# avip-mod_v3.net
KiCad netlist of a schematic drawn in EAGLE
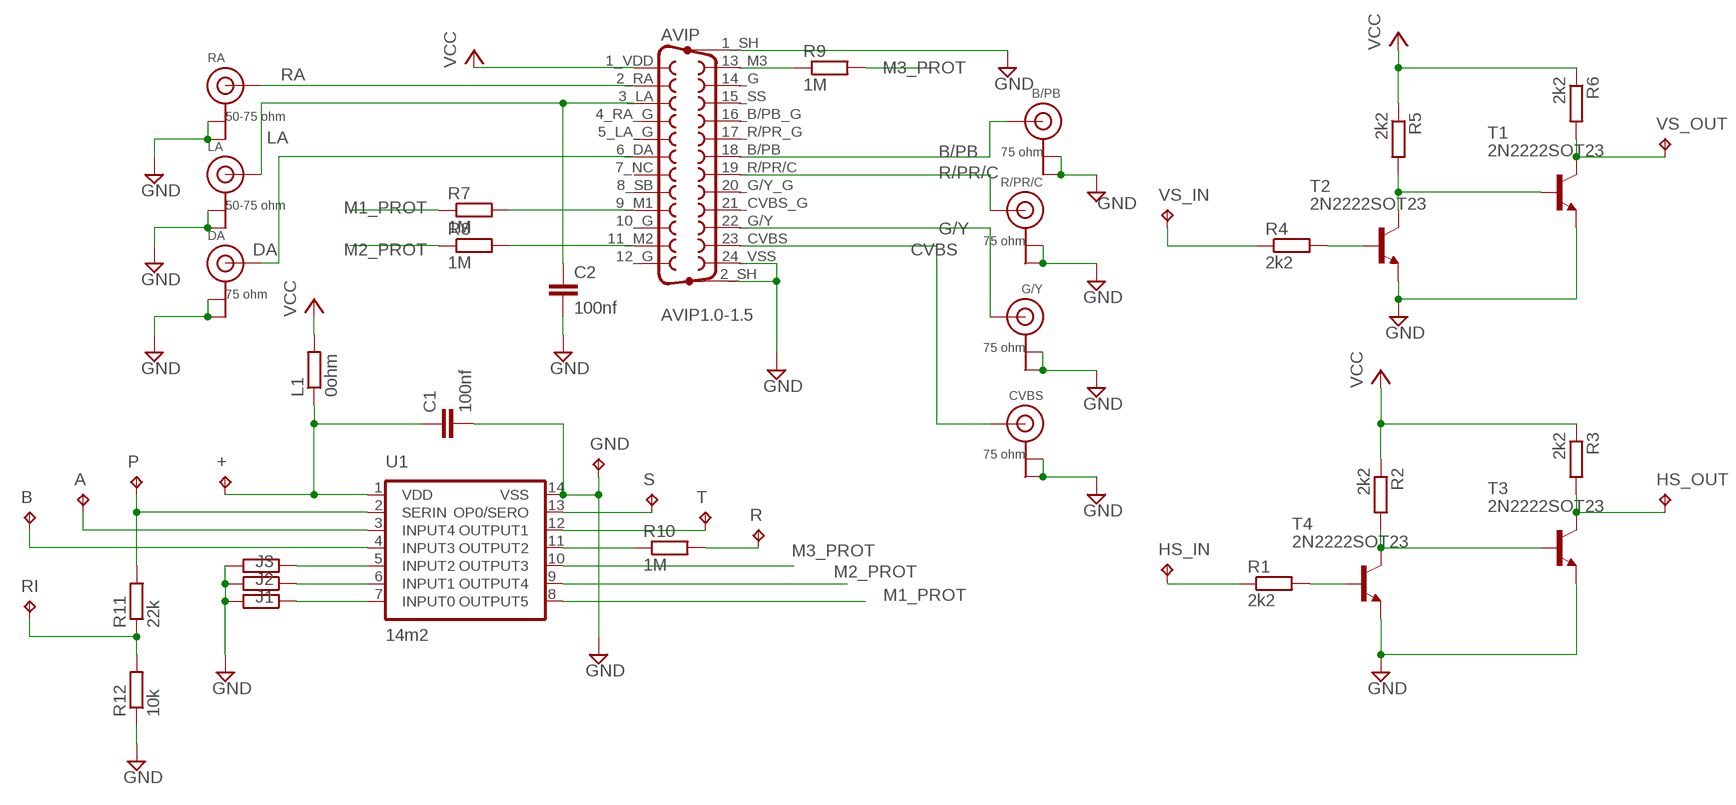
[diagram p0: schematic, sheet 1]

(export (version "E")
  (design (tool "Eeschema 10.0.6"))
  (components
    (comp (ref "+")
      (value "TPTP07SQ")
      (footprint "eagle-import:TP07SQ")
      (libsource (lib "eagle-import") (part "TPTP07SQ"))
    )
    (comp (ref "A")
      (value "TPTP07SQ")
      (footprint "eagle-import:TP07SQ")
      (libsource (lib "eagle-import") (part "TPTP07SQ"))
    )
    (comp (ref "AVIP")
      (value "AVIP1.0-1.5")
      (footprint "eagle-import:AVIP-1.0-1.5")
      (libsource (lib "eagle-import") (part "AVIP1.0-1.5"))
    )
    (comp (ref "B")
      (value "TPTP07SQ")
      (footprint "eagle-import:TP07SQ")
      (libsource (lib "eagle-import") (part "TPTP07SQ"))
    )
    (comp (ref "B/PB")
      (value "75 ohm")
      (footprint "eagle-import:U.FL")
      (libsource (lib "eagle-import") (part "ANTENNA_U.FL"))
    )
    (comp (ref "C1")
      (value "100nf")
      (footprint "eagle-import:C0603")
      (libsource (lib "eagle-import") (part "C-EUC0603"))
    )
    (comp (ref "C2")
      (value "100nf")
      (footprint "eagle-import:C0603")
      (libsource (lib "eagle-import") (part "C-EUC0603"))
    )
    (comp (ref "CVBS")
      (value "75 ohm")
      (footprint "eagle-import:U.FL")
      (libsource (lib "eagle-import") (part "ANTENNA_U.FL"))
    )
    (comp (ref "DA")
      (value "75 ohm")
      (footprint "eagle-import:U.FL")
      (libsource (lib "eagle-import") (part "ANTENNA_U.FL"))
    )
    (comp (ref "G/Y")
      (value "75 ohm")
      (footprint "eagle-import:U.FL")
      (libsource (lib "eagle-import") (part "ANTENNA_U.FL"))
    )
    (comp (ref "GND")
      (value "TPTP07SQ")
      (footprint "eagle-import:TP07SQ")
      (libsource (lib "eagle-import") (part "TPTP07SQ"))
    )
    (comp (ref "HS_IN")
      (value "TPTP07SQ")
      (footprint "eagle-import:TP07SQ")
      (libsource (lib "eagle-import") (part "TPTP07SQ"))
    )
    (comp (ref "HS_OUT")
      (value "TPTP07SQ")
      (footprint "eagle-import:TP07SQ")
      (libsource (lib "eagle-import") (part "TPTP07SQ"))
    )
    (comp (ref "J1")
      (value "0ohm")
      (footprint "eagle-import:R0603")
      (libsource (lib "eagle-import") (part "R-EU_R0603"))
    )
    (comp (ref "J2")
      (value "0ohm")
      (footprint "eagle-import:R0603")
      (libsource (lib "eagle-import") (part "R-EU_R0603"))
    )
    (comp (ref "J3")
      (value "0ohm")
      (footprint "eagle-import:R0603")
      (libsource (lib "eagle-import") (part "R-EU_R0603"))
    )
    (comp (ref "L1")
      (value "0ohm")
      (footprint "eagle-import:R0603")
      (libsource (lib "eagle-import") (part "R-EU_R0603"))
    )
    (comp (ref "LA")
      (value "50-75 ohm")
      (footprint "eagle-import:U.FL")
      (libsource (lib "eagle-import") (part "ANTENNA_U.FL"))
    )
    (comp (ref "P")
      (value "TPTP07SQ")
      (footprint "eagle-import:TP07SQ")
      (libsource (lib "eagle-import") (part "TPTP07SQ"))
    )
    (comp (ref "R")
      (value "TPTP07SQ")
      (footprint "eagle-import:TP07SQ")
      (libsource (lib "eagle-import") (part "TPTP07SQ"))
    )
    (comp (ref "R/PR/C")
      (value "75 ohm")
      (footprint "eagle-import:U.FL")
      (libsource (lib "eagle-import") (part "ANTENNA_U.FL"))
    )
    (comp (ref "R1")
      (value "2k2")
      (footprint "eagle-import:R0603")
      (libsource (lib "eagle-import") (part "R-EU_R0603"))
    )
    (comp (ref "R2")
      (value "2k2")
      (footprint "eagle-import:R0603")
      (libsource (lib "eagle-import") (part "R-EU_R0603"))
    )
    (comp (ref "R3")
      (value "2k2")
      (footprint "eagle-import:R0603")
      (libsource (lib "eagle-import") (part "R-EU_R0603"))
    )
    (comp (ref "R4")
      (value "2k2")
      (footprint "eagle-import:R0603")
      (libsource (lib "eagle-import") (part "R-EU_R0603"))
    )
    (comp (ref "R5")
      (value "2k2")
      (footprint "eagle-import:R0603")
      (libsource (lib "eagle-import") (part "R-EU_R0603"))
    )
    (comp (ref "R6")
      (value "2k2")
      (footprint "eagle-import:R0603")
      (libsource (lib "eagle-import") (part "R-EU_R0603"))
    )
    (comp (ref "R7")
      (value "1M")
      (footprint "eagle-import:R0603")
      (libsource (lib "eagle-import") (part "R-EU_R0603"))
    )
    (comp (ref "R8")
      (value "1M")
      (footprint "eagle-import:R0603")
      (libsource (lib "eagle-import") (part "R-EU_R0603"))
    )
    (comp (ref "R9")
      (value "1M")
      (footprint "eagle-import:R0603")
      (libsource (lib "eagle-import") (part "R-EU_R0603"))
    )
    (comp (ref "R10")
      (value "1M")
      (footprint "eagle-import:R0603")
      (libsource (lib "eagle-import") (part "R-EU_R0603"))
    )
    (comp (ref "R11")
      (value "22k")
      (footprint "eagle-import:R0603")
      (libsource (lib "eagle-import") (part "R-EU_R0603"))
    )
    (comp (ref "R12")
      (value "10k")
      (footprint "eagle-import:R0603")
      (libsource (lib "eagle-import") (part "R-EU_R0603"))
    )
    (comp (ref "RA")
      (value "50-75 ohm")
      (footprint "eagle-import:U.FL")
      (libsource (lib "eagle-import") (part "ANTENNA_U.FL"))
    )
    (comp (ref "RI")
      (value "TPTP07SQ")
      (footprint "eagle-import:TP07SQ")
      (libsource (lib "eagle-import") (part "TPTP07SQ"))
    )
    (comp (ref "S")
      (value "TPTP07SQ")
      (footprint "eagle-import:TP07SQ")
      (libsource (lib "eagle-import") (part "TPTP07SQ"))
    )
    (comp (ref "T")
      (value "TPTP07SQ")
      (footprint "eagle-import:TP07SQ")
      (libsource (lib "eagle-import") (part "TPTP07SQ"))
    )
    (comp (ref "T1")
      (value "2N2222SOT23")
      (footprint "eagle-import:SOT23")
      (libsource (lib "eagle-import") (part "2N2222SOT23"))
    )
    (comp (ref "T2")
      (value "2N2222SOT23")
      (footprint "eagle-import:SOT23")
      (libsource (lib "eagle-import") (part "2N2222SOT23"))
    )
    (comp (ref "T3")
      (value "2N2222SOT23")
      (footprint "eagle-import:SOT23")
      (libsource (lib "eagle-import") (part "2N2222SOT23"))
    )
    (comp (ref "T4")
      (value "2N2222SOT23")
      (footprint "eagle-import:SOT23")
      (libsource (lib "eagle-import") (part "2N2222SOT23"))
    )
    (comp (ref "U1")
      (value "14m2")
      (footprint "eagle-import:SO14")
      (libsource (lib "eagle-import") (part "PICAXE-14AXE017M2SM"))
    )
    (comp (ref "VS_IN")
      (value "TPTP07SQ")
      (footprint "eagle-import:TP07SQ")
      (libsource (lib "eagle-import") (part "TPTP07SQ"))
    )
    (comp (ref "VS_OUT")
      (value "TPTP07SQ")
      (footprint "eagle-import:TP07SQ")
      (libsource (lib "eagle-import") (part "TPTP07SQ"))
    )
  )
  (nets
    (net (code "1") (name "/B{slash}PB") (class "Default")
      (node (ref "AVIP") (pin "18_B/PB") (pinfunction "18_B/PB_18_B/PB") (pintype "passive"))
      (node (ref "B/PB") (pin "3") (pinfunction "SIGNAL_3") (pintype "passive"))
    )
    (net (code "2") (name "/CVBS") (class "Default")
      (node (ref "AVIP") (pin "23_CVBS") (pinfunction "23_CVBS_23_CVBS") (pintype "passive"))
      (node (ref "CVBS") (pin "3") (pinfunction "SIGNAL_3") (pintype "passive"))
    )
    (net (code "3") (name "/DA") (class "Default")
      (node (ref "AVIP") (pin "6_DA") (pinfunction "6_DA_6_DA") (pintype "passive"))
      (node (ref "DA") (pin "3") (pinfunction "SIGNAL_3") (pintype "passive"))
    )
    (net (code "4") (name "/G{slash}Y") (class "Default")
      (node (ref "AVIP") (pin "22_G/Y") (pinfunction "22_G/Y_22_G/Y") (pintype "passive"))
      (node (ref "G/Y") (pin "3") (pinfunction "SIGNAL_3") (pintype "passive"))
    )
    (net (code "5") (name "/LA") (class "Default")
      (node (ref "AVIP") (pin "3_LA") (pinfunction "3_LA_3_LA") (pintype "passive"))
      (node (ref "C2") (pin "1") (pinfunction "1_1") (pintype "passive"))
      (node (ref "LA") (pin "3") (pinfunction "SIGNAL_3") (pintype "passive"))
    )
    (net (code "6") (name "/M1_PROT") (class "Default")
      (node (ref "R7") (pin "1") (pinfunction "1_1") (pintype "passive"))
      (node (ref "U1") (pin "8") (pinfunction "OUTPUT5_8") (pintype "output"))
    )
    (net (code "7") (name "/M2_PROT") (class "Default")
      (node (ref "R8") (pin "1") (pinfunction "1_1") (pintype "passive"))
      (node (ref "U1") (pin "9") (pinfunction "OUTPUT4_9") (pintype "output"))
    )
    (net (code "8") (name "/M3_PROT") (class "Default")
      (node (ref "R9") (pin "2") (pinfunction "2_2") (pintype "passive"))
      (node (ref "U1") (pin "10") (pinfunction "OUTPUT3_10") (pintype "output"))
    )
    (net (code "9") (name "/RA") (class "Default")
      (node (ref "AVIP") (pin "2_RA") (pinfunction "2_RA_2_RA") (pintype "passive"))
      (node (ref "RA") (pin "3") (pinfunction "SIGNAL_3") (pintype "passive"))
    )
    (net (code "10") (name "/R{slash}PR{slash}C") (class "Default")
      (node (ref "AVIP") (pin "19_R/PR/C") (pinfunction "19_R/PR/C_19_R/PR/C") (pintype "passive"))
      (node (ref "R/PR/C") (pin "3") (pinfunction "SIGNAL_3") (pintype "passive"))
    )
    (net (code "11") (name "GND") (class "Default")
      (node (ref "AVIP") (pin "1_SH") (pinfunction "1_SH_1_SH") (pintype "passive"))
      (node (ref "AVIP") (pin "24_VSS") (pinfunction "24_VSS_24_VSS") (pintype "passive"))
      (node (ref "AVIP") (pin "2_SH") (pinfunction "2_SH_2_SH") (pintype "passive"))
      (node (ref "B/PB") (pin "1") (pinfunction "GND_1") (pintype "passive"))
      (node (ref "B/PB") (pin "2") (pinfunction "GND_2") (pintype "passive"))
      (node (ref "C1") (pin "2") (pinfunction "2_2") (pintype "passive"))
      (node (ref "C2") (pin "2") (pinfunction "2_2") (pintype "passive"))
      (node (ref "CVBS") (pin "1") (pinfunction "GND_1") (pintype "passive"))
      (node (ref "CVBS") (pin "2") (pinfunction "GND_2") (pintype "passive"))
      (node (ref "DA") (pin "1") (pinfunction "GND_1") (pintype "passive"))
      (node (ref "DA") (pin "2") (pinfunction "GND_2") (pintype "passive"))
      (node (ref "G/Y") (pin "1") (pinfunction "GND_1") (pintype "passive"))
      (node (ref "G/Y") (pin "2") (pinfunction "GND_2") (pintype "passive"))
      (node (ref "GND") (pin "TP") (pinfunction "TP_TP") (pintype "input"))
      (node (ref "J1") (pin "2") (pinfunction "2_2") (pintype "passive"))
      (node (ref "J2") (pin "2") (pinfunction "2_2") (pintype "passive"))
      (node (ref "J3") (pin "2") (pinfunction "2_2") (pintype "passive"))
      (node (ref "LA") (pin "1") (pinfunction "GND_1") (pintype "passive"))
      (node (ref "LA") (pin "2") (pinfunction "GND_2") (pintype "passive"))
      (node (ref "R/PR/C") (pin "1") (pinfunction "GND_1") (pintype "passive"))
      (node (ref "R/PR/C") (pin "2") (pinfunction "GND_2") (pintype "passive"))
      (node (ref "R12") (pin "1") (pinfunction "1_1") (pintype "passive"))
      (node (ref "RA") (pin "1") (pinfunction "GND_1") (pintype "passive"))
      (node (ref "RA") (pin "2") (pinfunction "GND_2") (pintype "passive"))
      (node (ref "T1") (pin "3") (pinfunction "E_3") (pintype "passive"))
      (node (ref "T2") (pin "3") (pinfunction "E_3") (pintype "passive"))
      (node (ref "T3") (pin "3") (pinfunction "E_3") (pintype "passive"))
      (node (ref "T4") (pin "3") (pinfunction "E_3") (pintype "passive"))
      (node (ref "U1") (pin "14") (pinfunction "VSS_14") (pintype "power_in"))
    )
    (net (code "12") (name "Net-(AVIP-Pad9_M1)") (class "Default")
      (node (ref "AVIP") (pin "9_M1") (pinfunction "9_M1_9_M1") (pintype "passive"))
      (node (ref "R7") (pin "2") (pinfunction "2_2") (pintype "passive"))
    )
    (net (code "13") (name "Net-(AVIP-Pad11_M2)") (class "Default")
      (node (ref "AVIP") (pin "11_M2") (pinfunction "11_M2_11_M2") (pintype "passive"))
      (node (ref "R8") (pin "2") (pinfunction "2_2") (pintype "passive"))
    )
    (net (code "14") (name "Net-(AVIP-Pad13_M3)") (class "Default")
      (node (ref "AVIP") (pin "13_M3") (pinfunction "13_M3_13_M3") (pintype "passive"))
      (node (ref "R9") (pin "1") (pinfunction "1_1") (pintype "passive"))
    )
    (net (code "15") (name "Net-(HS_IN-PadTP)") (class "Default")
      (node (ref "HS_IN") (pin "TP") (pinfunction "TP_TP") (pintype "input"))
      (node (ref "R1") (pin "1") (pinfunction "1_1") (pintype "passive"))
    )
    (net (code "16") (name "Net-(R-PadTP)") (class "Default")
      (node (ref "R") (pin "TP") (pinfunction "TP_TP") (pintype "input"))
      (node (ref "R10") (pin "2") (pinfunction "2_2") (pintype "passive"))
    )
    (net (code "17") (name "Net-(R4-Pad1)") (class "Default")
      (node (ref "R4") (pin "1") (pinfunction "1_1") (pintype "passive"))
      (node (ref "VS_IN") (pin "TP") (pinfunction "TP_TP") (pintype "input"))
    )
    (net (code "18") (name "Net-(R11-Pad1)") (class "Default")
      (node (ref "R11") (pin "1") (pinfunction "1_1") (pintype "passive"))
      (node (ref "R12") (pin "2") (pinfunction "2_2") (pintype "passive"))
      (node (ref "RI") (pin "TP") (pinfunction "TP_TP") (pintype "input"))
    )
    (net (code "19") (name "Net-(T1-B)") (class "Default")
      (node (ref "R5") (pin "2") (pinfunction "2_2") (pintype "passive"))
      (node (ref "T1") (pin "1") (pinfunction "B_1") (pintype "passive"))
      (node (ref "T2") (pin "2") (pinfunction "C_2") (pintype "passive"))
    )
    (net (code "20") (name "Net-(T1-C)") (class "Default")
      (node (ref "R6") (pin "2") (pinfunction "2_2") (pintype "passive"))
      (node (ref "T1") (pin "2") (pinfunction "C_2") (pintype "passive"))
      (node (ref "VS_OUT") (pin "TP") (pinfunction "TP_TP") (pintype "input"))
    )
    (net (code "21") (name "Net-(T2-B)") (class "Default")
      (node (ref "R4") (pin "2") (pinfunction "2_2") (pintype "passive"))
      (node (ref "T2") (pin "1") (pinfunction "B_1") (pintype "passive"))
    )
    (net (code "22") (name "Net-(T3-B)") (class "Default")
      (node (ref "R2") (pin "2") (pinfunction "2_2") (pintype "passive"))
      (node (ref "T3") (pin "1") (pinfunction "B_1") (pintype "passive"))
      (node (ref "T4") (pin "2") (pinfunction "C_2") (pintype "passive"))
    )
    (net (code "23") (name "Net-(T3-C)") (class "Default")
      (node (ref "HS_OUT") (pin "TP") (pinfunction "TP_TP") (pintype "input"))
      (node (ref "R3") (pin "2") (pinfunction "2_2") (pintype "passive"))
      (node (ref "T3") (pin "2") (pinfunction "C_2") (pintype "passive"))
    )
    (net (code "24") (name "Net-(T4-B)") (class "Default")
      (node (ref "R1") (pin "2") (pinfunction "2_2") (pintype "passive"))
      (node (ref "T4") (pin "1") (pinfunction "B_1") (pintype "passive"))
    )
    (net (code "25") (name "Net-(U1-INPUT0)") (class "Default")
      (node (ref "J1") (pin "1") (pinfunction "1_1") (pintype "passive"))
      (node (ref "U1") (pin "7") (pinfunction "INPUT0_7") (pintype "input"))
    )
    (net (code "26") (name "Net-(U1-INPUT1)") (class "Default")
      (node (ref "J2") (pin "1") (pinfunction "1_1") (pintype "passive"))
      (node (ref "U1") (pin "6") (pinfunction "INPUT1_6") (pintype "input"))
    )
    (net (code "27") (name "Net-(U1-INPUT2)") (class "Default")
      (node (ref "J3") (pin "1") (pinfunction "1_1") (pintype "passive"))
      (node (ref "U1") (pin "5") (pinfunction "INPUT2_5") (pintype "input"))
    )
    (net (code "28") (name "Net-(U1-INPUT3)") (class "Default")
      (node (ref "B") (pin "TP") (pinfunction "TP_TP") (pintype "input"))
      (node (ref "U1") (pin "4") (pinfunction "INPUT3_4") (pintype "input"))
    )
    (net (code "29") (name "Net-(U1-INPUT4)") (class "Default")
      (node (ref "A") (pin "TP") (pinfunction "TP_TP") (pintype "input"))
      (node (ref "U1") (pin "3") (pinfunction "INPUT4_3") (pintype "input"))
    )
    (net (code "30") (name "Net-(U1-OP0{slash}SERO)") (class "Default")
      (node (ref "S") (pin "TP") (pinfunction "TP_TP") (pintype "input"))
      (node (ref "U1") (pin "13") (pinfunction "OP0/SERO_13") (pintype "output"))
    )
    (net (code "31") (name "Net-(U1-OUTPUT1)") (class "Default")
      (node (ref "T") (pin "TP") (pinfunction "TP_TP") (pintype "input"))
      (node (ref "U1") (pin "12") (pinfunction "OUTPUT1_12") (pintype "output"))
    )
    (net (code "32") (name "Net-(U1-OUTPUT2)") (class "Default")
      (node (ref "R10") (pin "1") (pinfunction "1_1") (pintype "passive"))
      (node (ref "U1") (pin "11") (pinfunction "OUTPUT2_11") (pintype "output"))
    )
    (net (code "33") (name "Net-(U1-SERIN)") (class "Default")
      (node (ref "P") (pin "TP") (pinfunction "TP_TP") (pintype "input"))
      (node (ref "R11") (pin "2") (pinfunction "2_2") (pintype "passive"))
      (node (ref "U1") (pin "2") (pinfunction "SERIN_2") (pintype "input"))
    )
    (net (code "34") (name "Net-(U1-VDD)") (class "Default")
      (node (ref "+") (pin "TP") (pinfunction "TP_TP") (pintype "input"))
      (node (ref "C1") (pin "1") (pinfunction "1_1") (pintype "passive"))
      (node (ref "L1") (pin "1") (pinfunction "1_1") (pintype "passive"))
      (node (ref "U1") (pin "1") (pinfunction "VDD_1") (pintype "power_in"))
    )
    (net (code "35") (name "VCC") (class "Default")
      (node (ref "AVIP") (pin "1_VDD") (pinfunction "1_VDD_1_VDD") (pintype "power_in"))
      (node (ref "L1") (pin "2") (pinfunction "2_2") (pintype "passive"))
      (node (ref "R2") (pin "1") (pinfunction "1_1") (pintype "passive"))
      (node (ref "R3") (pin "1") (pinfunction "1_1") (pintype "passive"))
      (node (ref "R5") (pin "1") (pinfunction "1_1") (pintype "passive"))
      (node (ref "R6") (pin "1") (pinfunction "1_1") (pintype "passive"))
    )
    (net (code "36") (name "unconnected-(AVIP-Pad4_RA_G)") (class "Default")
      (node (ref "AVIP") (pin "4_RA_G") (pinfunction "4_RA_G_4_RA_G") (pintype "passive"))
    )
    (net (code "37") (name "unconnected-(AVIP-Pad5_LA_G)") (class "Default")
      (node (ref "AVIP") (pin "5_LA_G") (pinfunction "5_LA_G_5_LA_G") (pintype "passive"))
    )
    (net (code "38") (name "unconnected-(AVIP-Pad7_NC)") (class "Default")
      (node (ref "AVIP") (pin "7_NC") (pinfunction "7_NC_7_NC") (pintype "passive"))
    )
    (net (code "39") (name "unconnected-(AVIP-Pad8_SB)") (class "Default")
      (node (ref "AVIP") (pin "8_SB") (pinfunction "8_SB_8_SB") (pintype "passive"))
    )
    (net (code "40") (name "unconnected-(AVIP-Pad10_G)") (class "Default")
      (node (ref "AVIP") (pin "10_G") (pinfunction "10_G_10_G") (pintype "passive"))
    )
    (net (code "41") (name "unconnected-(AVIP-Pad12_G)") (class "Default")
      (node (ref "AVIP") (pin "12_G") (pinfunction "12_G_12_G") (pintype "passive"))
    )
    (net (code "42") (name "unconnected-(AVIP-Pad14_G)") (class "Default")
      (node (ref "AVIP") (pin "14_G") (pinfunction "14_G_14_G") (pintype "passive"))
    )
    (net (code "43") (name "unconnected-(AVIP-Pad15_SS)") (class "Default")
      (node (ref "AVIP") (pin "15_SS") (pinfunction "15_SS_15_SS") (pintype "passive"))
    )
    (net (code "44") (name "unconnected-(AVIP-Pad16_B{slash}PB_G)") (class "Default")
      (node (ref "AVIP") (pin "16_B/PB_G") (pinfunction "16_B/PB_G_16_B/PB_G") (pintype "passive"))
    )
    (net (code "45") (name "unconnected-(AVIP-Pad17_R{slash}PR_G)") (class "Default")
      (node (ref "AVIP") (pin "17_R/PR_G") (pinfunction "17_R/PR_G_17_R/PR_G") (pintype "passive"))
    )
    (net (code "46") (name "unconnected-(AVIP-Pad20_G{slash}Y_G)") (class "Default")
      (node (ref "AVIP") (pin "20_G/Y_G") (pinfunction "20_G/Y_G_20_G/Y_G") (pintype "passive"))
    )
    (net (code "47") (name "unconnected-(AVIP-Pad21_CVBS_G)") (class "Default")
      (node (ref "AVIP") (pin "21_CVBS_G") (pinfunction "21_CVBS_G_21_CVBS_G") (pintype "passive"))
    )
  )
)
